# ai_breakout_ft232RL_panel.net
KiCad netlist of a schematic drawn in EAGLE
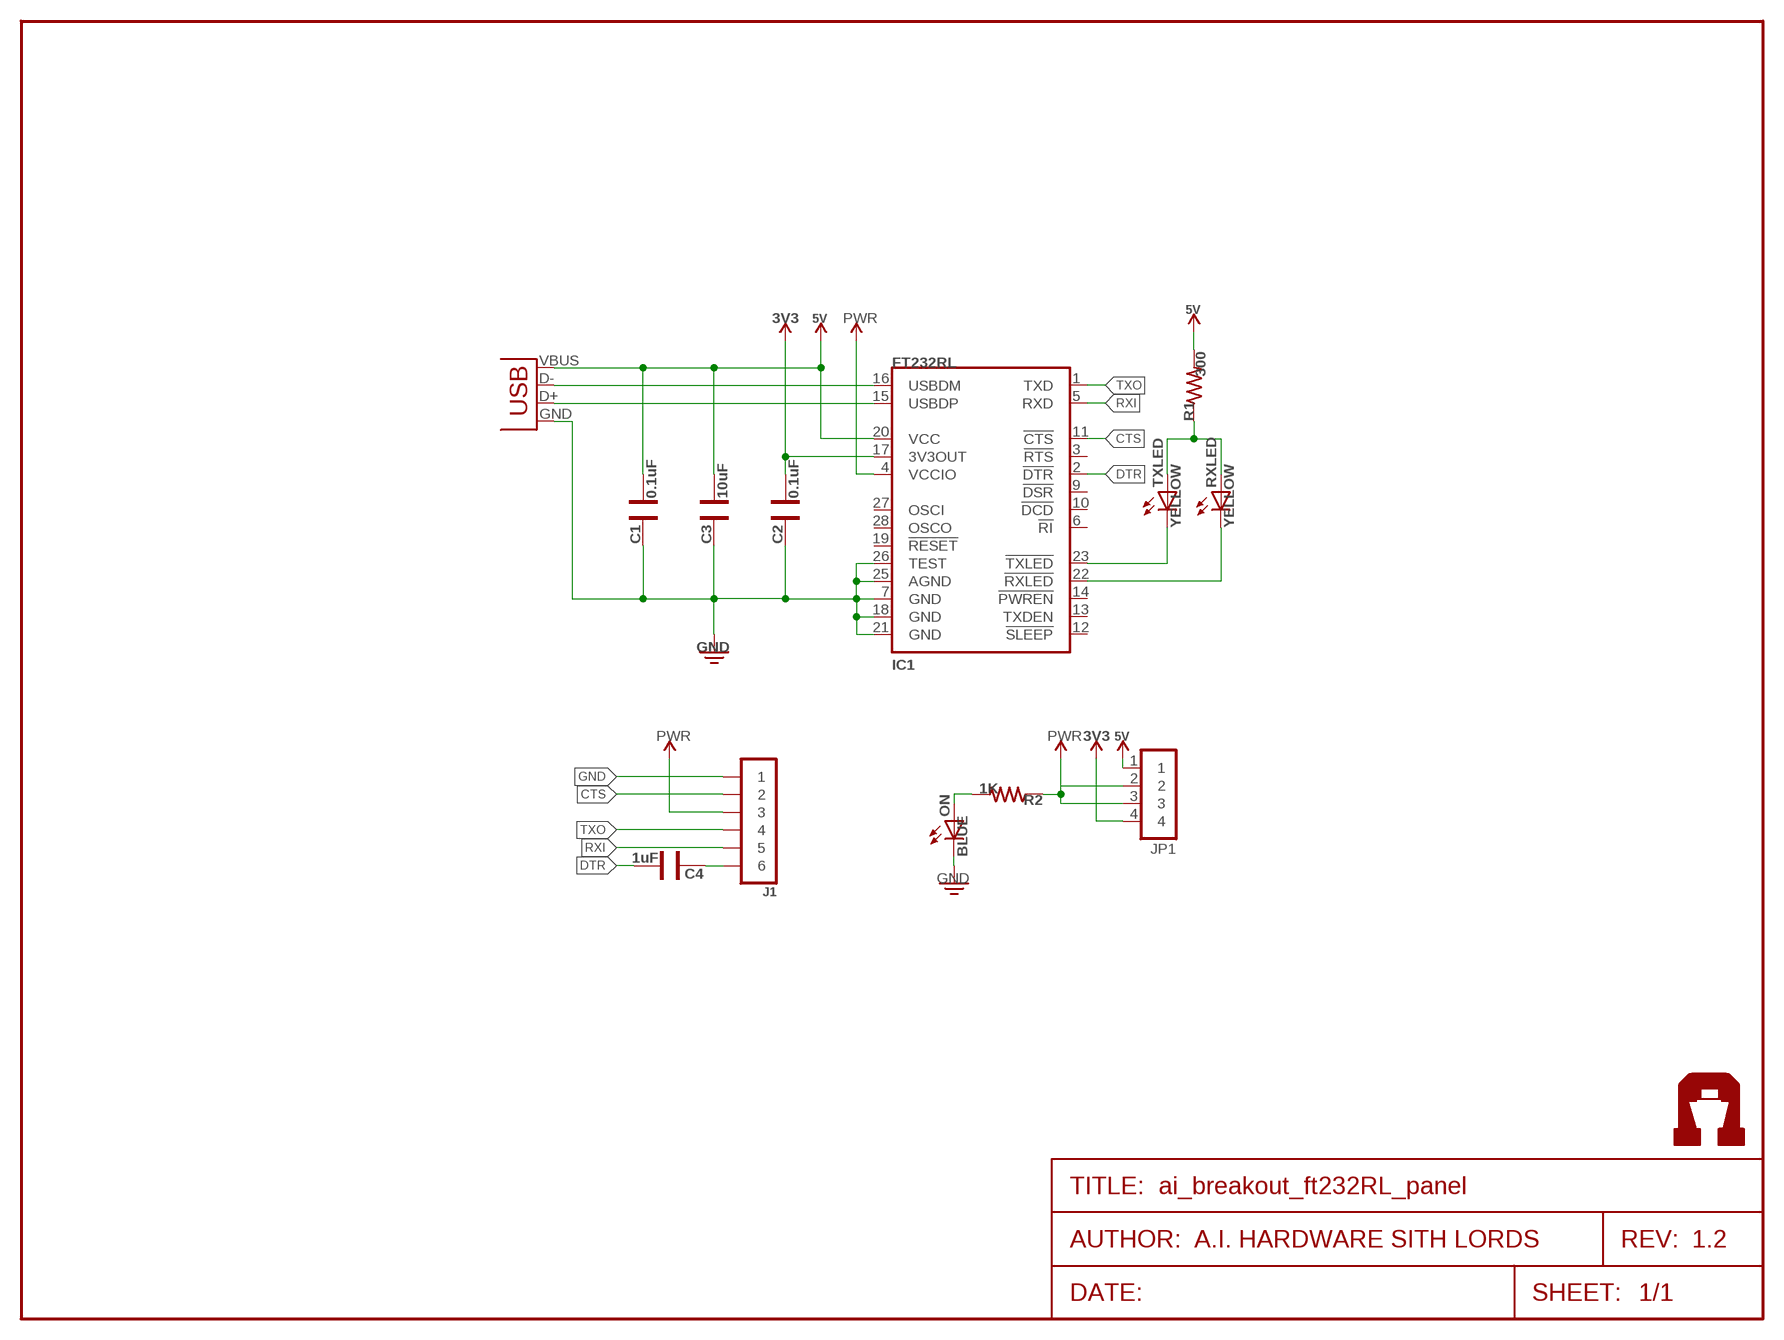
[diagram p0: schematic, sheet 1]

(export (version "E")
  (design (tool "Eeschema 10.0.6"))
  (components
    (comp (ref "C1")
      (value "0.1uF")
      (footprint "eagle-import:CAP-0603")
      (libsource (lib "eagle-import") (part "CAP0603"))
    )
    (comp (ref "C2")
      (value "0.1uF")
      (footprint "eagle-import:CAP-0603")
      (libsource (lib "eagle-import") (part "CAP0603"))
    )
    (comp (ref "C3")
      (value "10uF")
      (footprint "eagle-import:CAP-0603")
      (libsource (lib "eagle-import") (part "CAP0603"))
    )
    (comp (ref "C4")
      (value "1uF")
      (footprint "eagle-import:CAP-0603")
      (libsource (lib "eagle-import") (part "CAP0603"))
    )
    (comp (ref "IC1")
      (value "FT2332RL")
      (footprint "eagle-import:SSOP28-LD")
      (libsource (lib "eagle-import") (part "FT2332RL"))
    )
    (comp (ref "J1")
      (value "1X06LONG")
      (footprint "eagle-import:1X06-LONG")
      (libsource (lib "eagle-import") (part "1X06LONG"))
    )
    (comp (ref "JP1")
      (value "1X04NOSILK")
      (footprint "eagle-import:1X04-NOSILK")
      (libsource (lib "eagle-import") (part "1X04NOSILK"))
    )
    (comp (ref "ON")
      (value "BLUE")
      (footprint "eagle-import:LED-0603")
      (libsource (lib "eagle-import") (part "LED0603"))
    )
    (comp (ref "R1")
      (value "300")
      (footprint "eagle-import:RES-0603")
      (libsource (lib "eagle-import") (part "RES0603"))
    )
    (comp (ref "R2")
      (value "1K")
      (footprint "eagle-import:RES-0603")
      (libsource (lib "eagle-import") (part "RES0603"))
    )
    (comp (ref "RXLED")
      (value "YELLOW")
      (footprint "eagle-import:LED-0603")
      (libsource (lib "eagle-import") (part "LED0603"))
    )
    (comp (ref "TXLED")
      (value "YELLOW")
      (footprint "eagle-import:LED-0603")
      (libsource (lib "eagle-import") (part "LED0603"))
    )
    (comp (ref "U$3")
      (value "AI-LOGOL")
      (footprint "eagle-import:AI-LOGO-L")
      (libsource (lib "eagle-import") (part "AI-LOGOL"))
    )
    (comp (ref "USB1")
      (value "USBMICROB-TH")
      (footprint "eagle-import:USB-MICROB-TH")
      (libsource (lib "eagle-import") (part "USBMICROB-TH"))
    )
  )
  (nets
    (net (code "1") (name "3V3") (class "Default")
      (node (ref "C2") (pin "1") (pinfunction "1_1") (pintype "passive"))
      (node (ref "IC1") (pin "17") (pinfunction "3V3OUT_17") (pintype "power_in"))
      (node (ref "JP1") (pin "4") (pinfunction "4_4") (pintype "bidirectional"))
    )
    (net (code "2") (name "5V") (class "Default")
      (node (ref "C1") (pin "1") (pinfunction "1_1") (pintype "passive"))
      (node (ref "C3") (pin "1") (pinfunction "1_1") (pintype "passive"))
      (node (ref "IC1") (pin "20") (pinfunction "VCC_20") (pintype "power_in"))
      (node (ref "JP1") (pin "1") (pinfunction "1_1") (pintype "bidirectional"))
      (node (ref "R1") (pin "2") (pinfunction "2_2") (pintype "passive"))
      (node (ref "USB1") (pin "VBUS") (pinfunction "VBUS_VBUS") (pintype "bidirectional"))
    )
    (net (code "3") (name "CTS") (class "Default")
      (node (ref "IC1") (pin "11") (pinfunction "~{CTS}_11") (pintype "input"))
      (node (ref "J1") (pin "2") (pinfunction "2_2") (pintype "bidirectional"))
    )
    (net (code "4") (name "DTR") (class "Default")
      (node (ref "C4") (pin "1") (pinfunction "1_1") (pintype "passive"))
      (node (ref "IC1") (pin "2") (pinfunction "~{DTR}_2") (pintype "output"))
    )
    (net (code "5") (name "GND") (class "Default")
      (node (ref "C1") (pin "2") (pinfunction "2_2") (pintype "passive"))
      (node (ref "C2") (pin "2") (pinfunction "2_2") (pintype "passive"))
      (node (ref "C3") (pin "2") (pinfunction "2_2") (pintype "passive"))
      (node (ref "IC1") (pin "18") (pinfunction "GND_18") (pintype "power_in"))
      (node (ref "IC1") (pin "21") (pinfunction "GND_21") (pintype "power_in"))
      (node (ref "IC1") (pin "25") (pinfunction "AGND_25") (pintype "power_in"))
      (node (ref "IC1") (pin "26") (pinfunction "TEST_26") (pintype "input"))
      (node (ref "IC1") (pin "7") (pinfunction "GND_7") (pintype "power_in"))
      (node (ref "J1") (pin "1") (pinfunction "1_1") (pintype "bidirectional"))
      (node (ref "ON") (pin "C") (pinfunction "C_C") (pintype "passive"))
      (node (ref "USB1") (pin "GND") (pinfunction "GND_GND") (pintype "bidirectional"))
    )
    (net (code "6") (name "Net-(C4-Pad2)") (class "Default")
      (node (ref "C4") (pin "2") (pinfunction "2_2") (pintype "passive"))
      (node (ref "J1") (pin "6") (pinfunction "6_6") (pintype "bidirectional"))
    )
    (net (code "7") (name "Net-(IC1-USBDM)") (class "Default")
      (node (ref "IC1") (pin "16") (pinfunction "USBDM_16") (pintype "bidirectional"))
      (node (ref "USB1") (pin "D-") (pinfunction "D-_D-") (pintype "bidirectional"))
    )
    (net (code "8") (name "Net-(IC1-USBDP)") (class "Default")
      (node (ref "IC1") (pin "15") (pinfunction "USBDP_15") (pintype "bidirectional"))
      (node (ref "USB1") (pin "D+") (pinfunction "D+_D+") (pintype "bidirectional"))
    )
    (net (code "9") (name "Net-(IC1-~{RXLED})") (class "Default")
      (node (ref "IC1") (pin "22") (pinfunction "~{RXLED}_22") (pintype "input"))
      (node (ref "RXLED") (pin "C") (pinfunction "C_C") (pintype "passive"))
    )
    (net (code "10") (name "Net-(IC1-~{TXLED})") (class "Default")
      (node (ref "IC1") (pin "23") (pinfunction "~{TXLED}_23") (pintype "input"))
      (node (ref "TXLED") (pin "C") (pinfunction "C_C") (pintype "passive"))
    )
    (net (code "11") (name "Net-(ON-PadA)") (class "Default")
      (node (ref "ON") (pin "A") (pinfunction "A_A") (pintype "passive"))
      (node (ref "R2") (pin "2") (pinfunction "2_2") (pintype "passive"))
    )
    (net (code "12") (name "Net-(R1-Pad1)") (class "Default")
      (node (ref "R1") (pin "1") (pinfunction "1_1") (pintype "passive"))
      (node (ref "RXLED") (pin "A") (pinfunction "A_A") (pintype "passive"))
      (node (ref "TXLED") (pin "A") (pinfunction "A_A") (pintype "passive"))
    )
    (net (code "13") (name "PWR") (class "Default")
      (node (ref "IC1") (pin "4") (pinfunction "VCCIO_4") (pintype "power_in"))
      (node (ref "J1") (pin "3") (pinfunction "3_3") (pintype "bidirectional"))
      (node (ref "JP1") (pin "2") (pinfunction "2_2") (pintype "bidirectional"))
      (node (ref "JP1") (pin "3") (pinfunction "3_3") (pintype "bidirectional"))
      (node (ref "R2") (pin "1") (pinfunction "1_1") (pintype "passive"))
    )
    (net (code "14") (name "RXI") (class "Default")
      (node (ref "IC1") (pin "5") (pinfunction "RXD_5") (pintype "input"))
      (node (ref "J1") (pin "5") (pinfunction "5_5") (pintype "bidirectional"))
    )
    (net (code "15") (name "TXO") (class "Default")
      (node (ref "IC1") (pin "1") (pinfunction "TXD_1") (pintype "output"))
      (node (ref "J1") (pin "4") (pinfunction "4_4") (pintype "bidirectional"))
    )
    (net (code "16") (name "unconnected-(IC1-OSCI-Pad27)") (class "Default")
      (node (ref "IC1") (pin "27") (pinfunction "OSCI_27") (pintype "no_connect"))
    )
    (net (code "17") (name "unconnected-(IC1-OSCO-Pad28)") (class "Default")
      (node (ref "IC1") (pin "28") (pinfunction "OSCO_28") (pintype "output"))
    )
    (net (code "18") (name "unconnected-(IC1-TXDEN-Pad13)") (class "Default")
      (node (ref "IC1") (pin "13") (pinfunction "TXDEN_13") (pintype "no_connect"))
    )
    (net (code "19") (name "unconnected-(IC1-~{DCD}-Pad10)") (class "Default")
      (node (ref "IC1") (pin "10") (pinfunction "~{DCD}_10") (pintype "no_connect"))
    )
    (net (code "20") (name "unconnected-(IC1-~{DSR}-Pad9)") (class "Default")
      (node (ref "IC1") (pin "9") (pinfunction "~{DSR}_9") (pintype "no_connect"))
    )
    (net (code "21") (name "unconnected-(IC1-~{PWREN}-Pad14)") (class "Default")
      (node (ref "IC1") (pin "14") (pinfunction "~{PWREN}_14") (pintype "no_connect"))
    )
    (net (code "22") (name "unconnected-(IC1-~{RESET}-Pad19)") (class "Default")
      (node (ref "IC1") (pin "19") (pinfunction "~{RESET}_19") (pintype "no_connect"))
    )
    (net (code "23") (name "unconnected-(IC1-~{RI}-Pad6)") (class "Default")
      (node (ref "IC1") (pin "6") (pinfunction "~{RI}_6") (pintype "no_connect"))
    )
    (net (code "24") (name "unconnected-(IC1-~{RTS}-Pad3)") (class "Default")
      (node (ref "IC1") (pin "3") (pinfunction "~{RTS}_3") (pintype "output"))
    )
    (net (code "25") (name "unconnected-(IC1-~{SLEEP}-Pad12)") (class "Default")
      (node (ref "IC1") (pin "12") (pinfunction "~{SLEEP}_12") (pintype "no_connect"))
    )
  )
)
